# Mosfet_2HbridgeV2.net
KiCad netlist of a schematic drawn in EAGLE
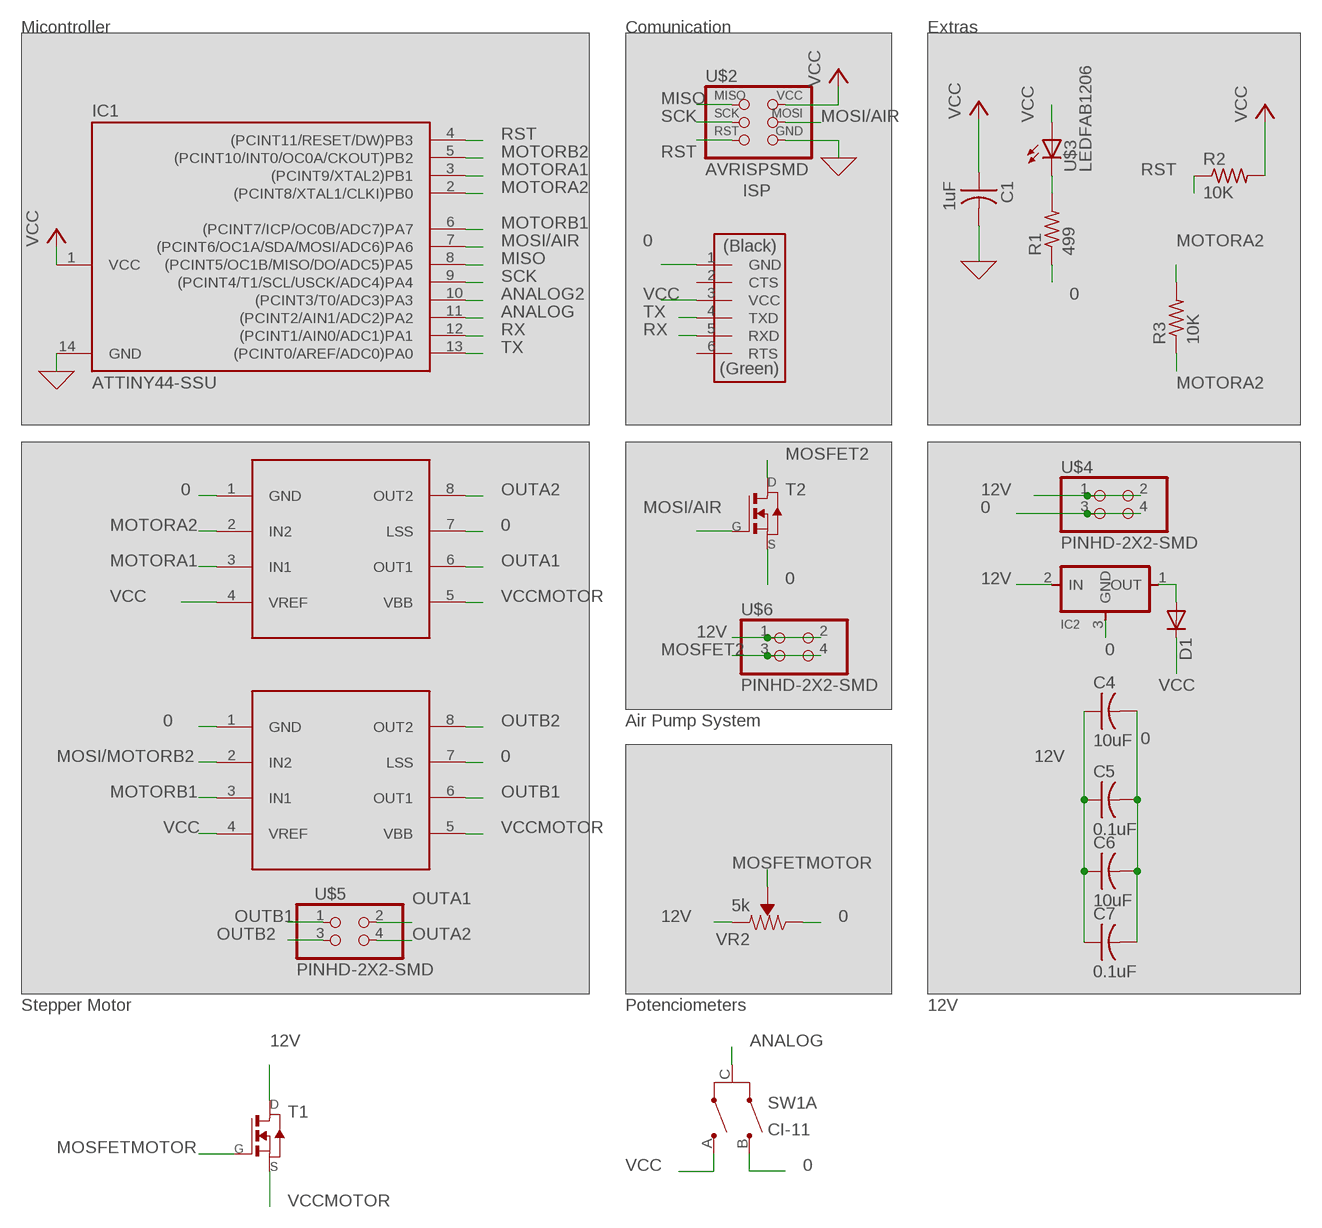
[diagram p0: schematic, sheet 1]

(export (version "E")
  (design (tool "Eeschema 10.0.6"))
  (components
    (comp (ref "C1")
      (value "1uF")
      (footprint "eagle-import:C1206FAB")
      (libsource (lib "eagle-import") (part "CAP-US1206FAB"))
    )
    (comp (ref "C4")
      (value "10uF")
      (footprint "eagle-import:C1206FAB")
      (libsource (lib "eagle-import") (part "CAP-US1206FAB"))
    )
    (comp (ref "C5")
      (value "0.1uF")
      (footprint "eagle-import:C1206FAB")
      (libsource (lib "eagle-import") (part "CAP-US1206FAB"))
    )
    (comp (ref "C6")
      (value "10uF")
      (footprint "eagle-import:C1206FAB")
      (libsource (lib "eagle-import") (part "CAP-US1206FAB"))
    )
    (comp (ref "C7")
      (value "0.1uF")
      (footprint "eagle-import:C1206FAB")
      (libsource (lib "eagle-import") (part "CAP-US1206FAB"))
    )
    (comp (ref "D1")
      (value "DIODESOD123")
      (footprint "eagle-import:SOD123")
      (libsource (lib "eagle-import") (part "DIODESOD123"))
    )
    (comp (ref "IC1")
      (value "ATTINY44-SSU")
      (footprint "eagle-import:SOIC14")
      (libsource (lib "eagle-import") (part "ATTINY44-SSU"))
    )
    (comp (ref "IC2")
      (value "REGULATORSOT23")
      (footprint "eagle-import:SOT23")
      (libsource (lib "eagle-import") (part "REGULATORSOT23"))
    )
    (comp (ref "R1")
      (value "499")
      (footprint "eagle-import:R1206FAB")
      (libsource (lib "eagle-import") (part "RES-US1206FAB"))
    )
    (comp (ref "R2")
      (value "10K")
      (footprint "eagle-import:R1206FAB")
      (libsource (lib "eagle-import") (part "RES-US1206FAB"))
    )
    (comp (ref "R3")
      (value "10K")
      (footprint "eagle-import:R1206FAB")
      (libsource (lib "eagle-import") (part "RES-US1206FAB"))
    )
    (comp (ref "SW1")
      (value "CI-11")
      (footprint "eagle-import:CI-11")
      (libsource (lib "eagle-import") (part "CI-11"))
    )
    (comp (ref "T1")
      (value "NMOSFETSOT23")
      (footprint "eagle-import:SOT-23")
      (libsource (lib "eagle-import") (part "NMOSFETSOT23"))
    )
    (comp (ref "T2")
      (value "NMOSFETSOT23")
      (footprint "eagle-import:SOT-23")
      (libsource (lib "eagle-import") (part "NMOSFETSOT23"))
    )
    (comp (ref "U$1")
      (value "FTDI-SMD-HEADER")
      (footprint "eagle-import:1X06SMD")
      (libsource (lib "eagle-import") (part "FTDI-SMD-HEADER"))
    )
    (comp (ref "U$2")
      (value "AVRISPSMD")
      (footprint "eagle-import:2X03SMD")
      (libsource (lib "eagle-import") (part "AVRISPSMD"))
    )
    (comp (ref "U$3")
      (value "LEDFAB1206")
      (footprint "eagle-import:LED1206FAB")
      (libsource (lib "eagle-import") (part "LEDFAB1206"))
    )
    (comp (ref "U$4")
      (value "PINHD-2X2-SMD")
      (footprint "eagle-import:2X02SMD")
      (libsource (lib "eagle-import") (part "PINHD-2X2-SMD"))
    )
    (comp (ref "U$5")
      (value "PINHD-2X2-SMD")
      (footprint "eagle-import:2X02SMD")
      (libsource (lib "eagle-import") (part "PINHD-2X2-SMD"))
    )
    (comp (ref "U$6")
      (value "PINHD-2X2-SMD")
      (footprint "eagle-import:2X02SMD")
      (libsource (lib "eagle-import") (part "PINHD-2X2-SMD"))
    )
    (comp (ref "U$7")
      (value "A4953-H-BRIDGE-MOTOR-DRIVER")
      (footprint "eagle-import:SOIC8")
      (libsource (lib "eagle-import") (part "A4953-H-BRIDGE-MOTOR-DRIVER"))
    )
    (comp (ref "U$8")
      (value "A4953-H-BRIDGE-MOTOR-DRIVER")
      (footprint "eagle-import:SOIC8")
      (libsource (lib "eagle-import") (part "A4953-H-BRIDGE-MOTOR-DRIVER"))
    )
    (comp (ref "VR2")
      (value "5k")
      (footprint "eagle-import:TRIMPOT-SMD-5MM")
      (libsource (lib "eagle-import") (part "TRIMPOT-SMD-5MM-CLOSED-1/4W-20%"))
    )
  )
  (nets
    (net (code "1") (name "/12V") (class "Default")
      (node (ref "C4") (pin "1") (pinfunction "1_1") (pintype "passive"))
      (node (ref "C5") (pin "1") (pinfunction "1_1") (pintype "passive"))
      (node (ref "C6") (pin "1") (pinfunction "1_1") (pintype "passive"))
      (node (ref "C7") (pin "1") (pinfunction "1_1") (pintype "passive"))
      (node (ref "IC2") (pin "2") (pinfunction "IN_2") (pintype "bidirectional"))
      (node (ref "T1") (pin "1") (pinfunction "D_1") (pintype "passive"))
      (node (ref "U$4") (pin "1") (pinfunction "1_1") (pintype "passive"))
      (node (ref "U$4") (pin "2") (pinfunction "2_2") (pintype "passive"))
      (node (ref "U$6") (pin "1") (pinfunction "1_1") (pintype "passive"))
      (node (ref "U$6") (pin "2") (pinfunction "2_2") (pintype "passive"))
      (node (ref "VR2") (pin "A") (pinfunction "CCW_A") (pintype "passive"))
    )
    (net (code "2") (name "/ANALOG") (class "Default")
      (node (ref "IC1") (pin "11") (pinfunction "(PCINT2/AIN1/ADC2)PA2_11") (pintype "bidirectional"))
      (node (ref "SW1") (pin "C") (pinfunction "C_C") (pintype "passive"))
    )
    (net (code "3") (name "/ANALOG2") (class "Default")
      (node (ref "IC1") (pin "10") (pinfunction "(PCINT3/T0/ADC3)PA3_10") (pintype "bidirectional"))
    )
    (net (code "4") (name "/MISO") (class "Default")
      (node (ref "IC1") (pin "8") (pinfunction "(PCINT5/OC1B/MISO/DO/ADC5)PA5_8") (pintype "bidirectional"))
      (node (ref "U$2") (pin "1") (pinfunction "MISO_1") (pintype "passive"))
    )
    (net (code "5") (name "/MOSFET2") (class "Default")
      (node (ref "T2") (pin "1") (pinfunction "D_1") (pintype "passive"))
      (node (ref "U$6") (pin "3") (pinfunction "3_3") (pintype "passive"))
      (node (ref "U$6") (pin "4") (pinfunction "4_4") (pintype "passive"))
    )
    (net (code "6") (name "/MOSFETMOTOR") (class "Default")
      (node (ref "T1") (pin "3") (pinfunction "G_3") (pintype "passive"))
      (node (ref "VR2") (pin "B") (pinfunction "WIPER_B") (pintype "passive"))
    )
    (net (code "7") (name "/MOSI{slash}AIR") (class "Default")
      (node (ref "IC1") (pin "7") (pinfunction "(PCINT6/OC1A/SDA/MOSI/ADC6)PA6_7") (pintype "bidirectional"))
      (node (ref "T2") (pin "3") (pinfunction "G_3") (pintype "passive"))
      (node (ref "U$2") (pin "4") (pinfunction "MOSI_4") (pintype "passive"))
    )
    (net (code "8") (name "/MOSI{slash}MOTORB2") (class "Default")
      (node (ref "U$7") (pin "2") (pinfunction "IN2_2") (pintype "bidirectional"))
    )
    (net (code "9") (name "/MOTORA1") (class "Default")
      (node (ref "IC1") (pin "3") (pinfunction "(PCINT9/XTAL2)PB1_3") (pintype "bidirectional"))
      (node (ref "U$8") (pin "3") (pinfunction "IN1_3") (pintype "bidirectional"))
    )
    (net (code "10") (name "/MOTORA2") (class "Default")
      (node (ref "IC1") (pin "2") (pinfunction "(PCINT8/XTAL1/CLKI)PB0_2") (pintype "bidirectional"))
      (node (ref "R3") (pin "1") (pinfunction "1_1") (pintype "passive"))
      (node (ref "R3") (pin "2") (pinfunction "2_2") (pintype "passive"))
      (node (ref "U$8") (pin "2") (pinfunction "IN2_2") (pintype "bidirectional"))
    )
    (net (code "11") (name "/MOTORB1") (class "Default")
      (node (ref "IC1") (pin "6") (pinfunction "(PCINT7/ICP/OC0B/ADC7)PA7_6") (pintype "bidirectional"))
      (node (ref "U$7") (pin "3") (pinfunction "IN1_3") (pintype "bidirectional"))
    )
    (net (code "12") (name "/MOTORB2") (class "Default")
      (node (ref "IC1") (pin "5") (pinfunction "(PCINT10/INT0/OC0A/CKOUT)PB2_5") (pintype "bidirectional"))
    )
    (net (code "13") (name "/OUTA1") (class "Default")
      (node (ref "U$5") (pin "2") (pinfunction "2_2") (pintype "passive"))
      (node (ref "U$8") (pin "6") (pinfunction "OUT1_6") (pintype "bidirectional"))
    )
    (net (code "14") (name "/OUTA2") (class "Default")
      (node (ref "U$5") (pin "4") (pinfunction "4_4") (pintype "passive"))
      (node (ref "U$8") (pin "8") (pinfunction "OUT2_8") (pintype "bidirectional"))
    )
    (net (code "15") (name "/OUTB1") (class "Default")
      (node (ref "U$5") (pin "1") (pinfunction "1_1") (pintype "passive"))
      (node (ref "U$7") (pin "6") (pinfunction "OUT1_6") (pintype "bidirectional"))
    )
    (net (code "16") (name "/OUTB2") (class "Default")
      (node (ref "U$5") (pin "3") (pinfunction "3_3") (pintype "passive"))
      (node (ref "U$7") (pin "8") (pinfunction "OUT2_8") (pintype "bidirectional"))
    )
    (net (code "17") (name "/RST") (class "Default")
      (node (ref "IC1") (pin "4") (pinfunction "(PCINT11/RESET/DW)PB3_4") (pintype "bidirectional"))
      (node (ref "R2") (pin "1") (pinfunction "1_1") (pintype "passive"))
      (node (ref "U$2") (pin "5") (pinfunction "RST_5") (pintype "passive"))
    )
    (net (code "18") (name "/RX") (class "Default")
      (node (ref "IC1") (pin "12") (pinfunction "(PCINT1/AIN0/ADC1)PA1_12") (pintype "bidirectional"))
      (node (ref "U$1") (pin "5") (pinfunction "RXD_5") (pintype "bidirectional"))
    )
    (net (code "19") (name "/SCK") (class "Default")
      (node (ref "IC1") (pin "9") (pinfunction "(PCINT4/T1/SCL/USCK/ADC4)PA4_9") (pintype "bidirectional"))
      (node (ref "U$2") (pin "3") (pinfunction "SCK_3") (pintype "passive"))
    )
    (net (code "20") (name "/TX") (class "Default")
      (node (ref "IC1") (pin "13") (pinfunction "(PCINT0/AREF/ADC0)PA0_13") (pintype "bidirectional"))
      (node (ref "U$1") (pin "4") (pinfunction "TXD_4") (pintype "bidirectional"))
    )
    (net (code "21") (name "/VCCMOTOR") (class "Default")
      (node (ref "T1") (pin "2") (pinfunction "S_2") (pintype "passive"))
      (node (ref "U$7") (pin "5") (pinfunction "VBB_5") (pintype "bidirectional"))
      (node (ref "U$8") (pin "5") (pinfunction "VBB_5") (pintype "bidirectional"))
    )
    (net (code "22") (name "GND") (class "Default")
      (node (ref "C1") (pin "2") (pinfunction "2_2") (pintype "passive"))
      (node (ref "C4") (pin "2") (pinfunction "2_2") (pintype "passive"))
      (node (ref "C5") (pin "2") (pinfunction "2_2") (pintype "passive"))
      (node (ref "C6") (pin "2") (pinfunction "2_2") (pintype "passive"))
      (node (ref "C7") (pin "2") (pinfunction "2_2") (pintype "passive"))
      (node (ref "IC1") (pin "14") (pinfunction "GND_14") (pintype "power_in"))
      (node (ref "IC2") (pin "3") (pinfunction "GND_3") (pintype "bidirectional"))
      (node (ref "R1") (pin "1") (pinfunction "1_1") (pintype "passive"))
      (node (ref "SW1") (pin "B") (pinfunction "B_B") (pintype "passive"))
      (node (ref "T2") (pin "2") (pinfunction "S_2") (pintype "passive"))
      (node (ref "U$1") (pin "1") (pinfunction "GND_1") (pintype "bidirectional"))
      (node (ref "U$2") (pin "6") (pinfunction "GND_6") (pintype "passive"))
      (node (ref "U$4") (pin "3") (pinfunction "3_3") (pintype "passive"))
      (node (ref "U$4") (pin "4") (pinfunction "4_4") (pintype "passive"))
      (node (ref "U$7") (pin "1") (pinfunction "GND_1") (pintype "bidirectional"))
      (node (ref "U$7") (pin "7") (pinfunction "LSS_7") (pintype "bidirectional"))
      (node (ref "U$8") (pin "1") (pinfunction "GND_1") (pintype "bidirectional"))
      (node (ref "U$8") (pin "7") (pinfunction "LSS_7") (pintype "bidirectional"))
      (node (ref "VR2") (pin "C") (pinfunction "CW_C") (pintype "passive"))
    )
    (net (code "23") (name "Net-(D1-A)") (class "Default")
      (node (ref "D1") (pin "ANODE") (pinfunction "A_ANODE") (pintype "passive"))
      (node (ref "IC2") (pin "1") (pinfunction "OUT_1") (pintype "bidirectional"))
    )
    (net (code "24") (name "Net-(U$3-C)") (class "Default")
      (node (ref "R1") (pin "2") (pinfunction "2_2") (pintype "passive"))
      (node (ref "U$3") (pin "2") (pinfunction "C_2") (pintype "passive"))
    )
    (net (code "25") (name "VCC") (class "Default")
      (node (ref "C1") (pin "1") (pinfunction "1_1") (pintype "passive"))
      (node (ref "D1") (pin "CATHODE") (pinfunction "C_CATHODE") (pintype "passive"))
      (node (ref "IC1") (pin "1") (pinfunction "VCC_1") (pintype "power_in"))
      (node (ref "R2") (pin "2") (pinfunction "2_2") (pintype "passive"))
      (node (ref "SW1") (pin "A") (pinfunction "A_A") (pintype "passive"))
      (node (ref "U$1") (pin "3") (pinfunction "VCC_3") (pintype "bidirectional"))
      (node (ref "U$2") (pin "2") (pinfunction "VCC_2") (pintype "passive"))
      (node (ref "U$3") (pin "1") (pinfunction "A_1") (pintype "passive"))
      (node (ref "U$7") (pin "4") (pinfunction "VREF_4") (pintype "bidirectional"))
      (node (ref "U$8") (pin "4") (pinfunction "VREF_4") (pintype "bidirectional"))
    )
    (net (code "26") (name "unconnected-(U$1-CTS-Pad2)") (class "Default")
      (node (ref "U$1") (pin "2") (pinfunction "CTS_2") (pintype "bidirectional"))
    )
    (net (code "27") (name "unconnected-(U$1-RTS-Pad6)") (class "Default")
      (node (ref "U$1") (pin "6") (pinfunction "RTS_6") (pintype "bidirectional"))
    )
  )
)
